# Clock_Distribution_PLL.net
KiCad netlist of a schematic drawn in Altium Designer
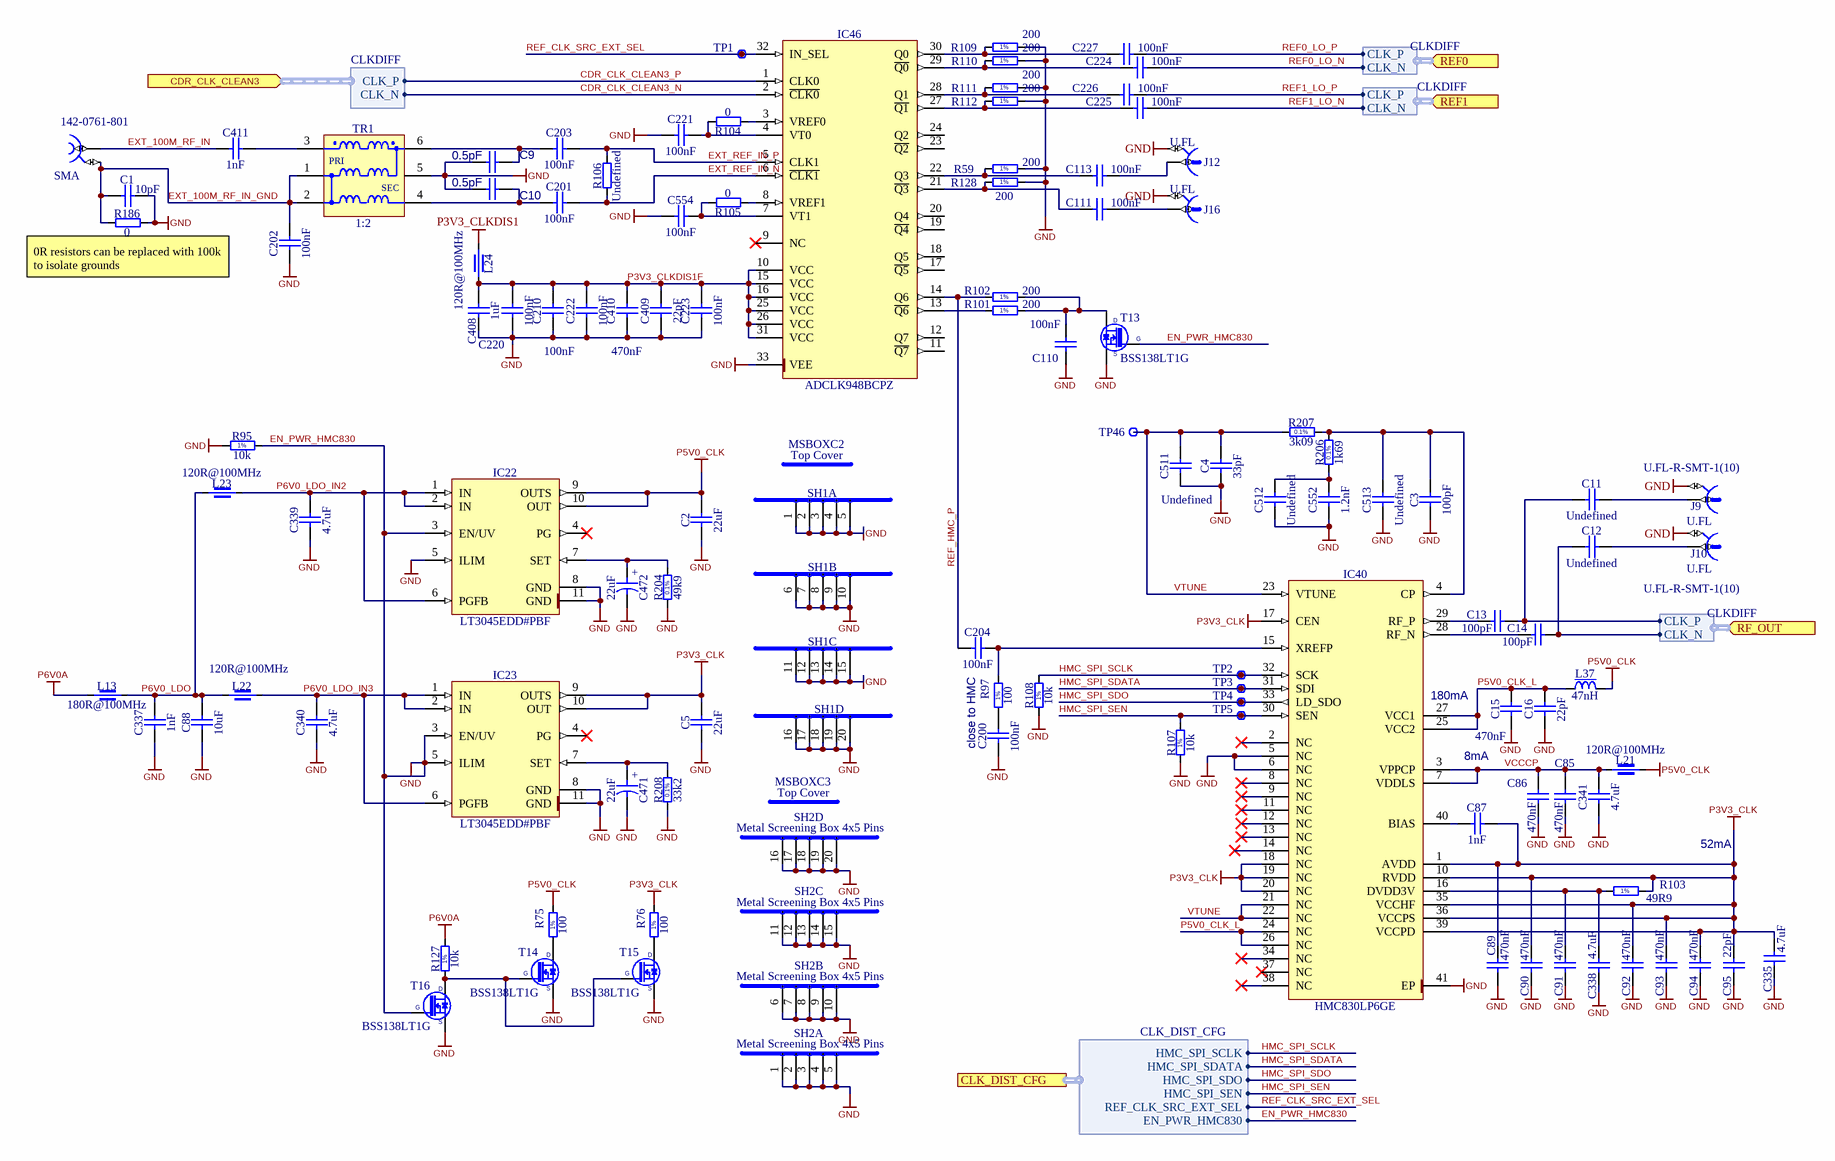
[diagram p0: Clock_Distribution_PLL.SchDoc]

(export (version "E")
  (design (tool "Eeschema 10.0.6"))
  (components
    (comp (ref "C1")
      (value "10pF")
      (footprint "CAPC1608X87N")
      (description "Non-polarised capacitor")
      (fields
        (field (name "MANUFACTURER PART NUMBER") "CC0603_10PF_50V_5%_NP0")
        (field (name "MANUFACTURER") "GENERIC")
        (field (name "AUTHOR") "CERN DEM JLC")
      )
      (libsource (lib "Capacitors") (part "Capacitor - non polarized"))
    )
    (comp (ref "C2")
      (value "22uF")
      (footprint "CAPC2012X135N")
      (description "Non-polarised capacitor")
      (fields
        (field (name "MANUFACTURER PART NUMBER") "CC0805_22UF_16V_10%_X5R")
        (field (name "MANUFACTURER") "GENERIC")
        (field (name "AUTHOR") "CERN DEM JLC")
      )
      (libsource (lib "Capacitors") (part "Capacitor - non polarized"))
    )
    (comp (ref "C3")
      (value "100pF")
      (footprint "CAPC1608X87N")
      (description "Non-polarised capacitor")
      (fields
        (field (name "MANUFACTURER PART NUMBER") "CC0603_100PF_50V_5%_NP0")
        (field (name "MANUFACTURER") "GENERIC")
        (field (name "AUTHOR") "CERN DEM JLC")
      )
      (libsource (lib "Capacitors") (part "Capacitor - non polarized"))
    )
    (comp (ref "C4")
      (value "33pF")
      (footprint "CAPC1608X87N")
      (description "Non-polarised capacitor")
      (fields
        (field (name "MANUFACTURER PART NUMBER") "CC0603_33PF_50V_5%_NP0")
        (field (name "MANUFACTURER") "GENERIC")
        (field (name "AUTHOR") "CERN DEM JLC")
      )
      (libsource (lib "Capacitors") (part "Capacitor - non polarized"))
    )
    (comp (ref "C5")
      (value "22uF")
      (footprint "CAPC2012X135N")
      (description "Non-polarised capacitor")
      (fields
        (field (name "MANUFACTURER PART NUMBER") "CC0805_22UF_16V_10%_X5R")
        (field (name "MANUFACTURER") "GENERIC")
        (field (name "AUTHOR") "CERN DEM JLC")
      )
      (libsource (lib "Capacitors") (part "Capacitor - non polarized"))
    )
    (comp (ref "C9")
      (value "0.5pF")
      (footprint "CAPC1005X55N")
      (fields
        (field (name "$$NOTCOMMONPROPERTY_GENERAL PART NUMBER") "CC0402_0.5PF_25V_0.25PF_C0G")
        (field (name "MANUFACTURER PART NUMBER") "CC0402_0.5PF_25V_0.05PF_C0G")
        (field (name "MANUFACTURER") "GENERIC")
      )
      (libsource (lib "altium-import") (part "root_0__*"))
    )
    (comp (ref "C10")
      (value "0.5pF")
      (footprint "CAPC1005X55N")
      (fields
        (field (name "$$NOTCOMMONPROPERTY_GENERAL PART NUMBER") "CC0402_0.5PF_25V_0.25PF_C0G")
        (field (name "MANUFACTURER PART NUMBER") "CC0402_0.5PF_25V_0.05PF_C0G")
        (field (name "MANUFACTURER") "GENERIC")
      )
      (libsource (lib "altium-import") (part "root_0__*"))
    )
    (comp (ref "C11")
      (value "Undefined")
      (footprint "CAPC1005X55N")
      (description "Non-polarised capacitor")
      (fields (field (name "PART NUMBER") "CC0402_NO-VALUE") (field (name "AUTHOR") "CERN DEM JLC"))
      (libsource (lib "Capacitors") (part "Capacitor - non polarized"))
    )
    (comp (ref "C12")
      (value "Undefined")
      (footprint "CAPC1005X55N")
      (description "Non-polarised capacitor")
      (fields (field (name "PART NUMBER") "CC0402_NO-VALUE") (field (name "AUTHOR") "CERN DEM JLC"))
      (libsource (lib "Capacitors") (part "Capacitor - non polarized"))
    )
    (comp (ref "C13")
      (value "100pF")
      (footprint "CAPC1608X87N")
      (description "Non-polarised capacitor")
      (fields
        (field (name "MANUFACTURER PART NUMBER") "CC0603_100PF_50V_5%_NP0")
        (field (name "MANUFACTURER") "GENERIC")
        (field (name "AUTHOR") "CERN DEM JLC")
      )
      (libsource (lib "Capacitors") (part "Capacitor - non polarized"))
    )
    (comp (ref "C14")
      (value "100pF")
      (footprint "CAPC1608X87N")
      (description "Non-polarised capacitor")
      (fields
        (field (name "MANUFACTURER PART NUMBER") "CC0603_100PF_50V_5%_NP0")
        (field (name "MANUFACTURER") "GENERIC")
        (field (name "AUTHOR") "CERN DEM JLC")
      )
      (libsource (lib "Capacitors") (part "Capacitor - non polarized"))
    )
    (comp (ref "C15")
      (value "470nF")
      (footprint "CAPC1005X55N")
      (description "Non-polarised capacitor")
      (fields
        (field (name "MANUFACTURER PART NUMBER") "CC0402_470NF_16V_10%_X5R")
        (field (name "MANUFACTURER") "GENERIC")
        (field (name "AUTHOR") "CERN DEM JLC")
      )
      (libsource (lib "Capacitors") (part "Capacitor - non polarized"))
    )
    (comp (ref "C16")
      (value "22pF")
      (footprint "CAPC1005X55N")
      (description "Non-polarised capacitor")
      (fields
        (field (name "MANUFACTURER PART NUMBER") "CC0402_22PF_50V_5%_C0G")
        (field (name "MANUFACTURER") "GENERIC")
        (field (name "AUTHOR") "CERN DEM JLC")
      )
      (libsource (lib "Capacitors") (part "Capacitor - non polarized"))
    )
    (comp (ref "C85")
      (value "470nF")
      (footprint "CAPC1005X55N")
      (description "Non-polarised capacitor")
      (fields
        (field (name "MANUFACTURER PART NUMBER") "CC0402_470NF_16V_10%_X5R")
        (field (name "MANUFACTURER") "GENERIC")
        (field (name "AUTHOR") "CERN DEM JLC")
      )
      (libsource (lib "Capacitors") (part "Capacitor - non polarized"))
    )
    (comp (ref "C86")
      (value "470nF")
      (footprint "CAPC1005X55N")
      (description "Non-polarised capacitor")
      (fields
        (field (name "MANUFACTURER PART NUMBER") "CC0402_470NF_16V_10%_X5R")
        (field (name "MANUFACTURER") "GENERIC")
        (field (name "AUTHOR") "CERN DEM JLC")
      )
      (libsource (lib "Capacitors") (part "Capacitor - non polarized"))
    )
    (comp (ref "C87")
      (value "1nF")
      (footprint "CAPC1005X55N")
      (description "Non-polarised capacitor")
      (fields
        (field (name "MANUFACTURER PART NUMBER") "CC0402_1NF_50V_10%_X7R")
        (field (name "MANUFACTURER") "GENERIC")
        (field (name "AUTHOR") "CERN DEM JLC")
      )
      (libsource (lib "Capacitors") (part "Capacitor - non polarized"))
    )
    (comp (ref "C88")
      (value "10uF")
      (footprint "CAPC3216X180N")
      (description "Non-polarised capacitor")
      (fields
        (field (name "MANUFACTURER PART NUMBER") "CC1206_10uF_25V_10%_X7R")
        (field (name "MANUFACTURER") "GENERIC")
        (field (name "AUTHOR") "CERN DEM JLC")
      )
      (libsource (lib "Capacitors") (part "Capacitor - non polarized"))
    )
    (comp (ref "C89")
      (value "470nF")
      (footprint "CAPC1005X55N")
      (description "Non-polarised capacitor")
      (fields
        (field (name "MANUFACTURER PART NUMBER") "CC0402_470NF_16V_10%_X5R")
        (field (name "MANUFACTURER") "GENERIC")
        (field (name "AUTHOR") "CERN DEM JLC")
      )
      (libsource (lib "Capacitors") (part "Capacitor - non polarized"))
    )
    (comp (ref "C90")
      (value "470nF")
      (footprint "CAPC1005X55N")
      (description "Non-polarised capacitor")
      (fields
        (field (name "MANUFACTURER PART NUMBER") "CC0402_470NF_16V_10%_X5R")
        (field (name "MANUFACTURER") "GENERIC")
        (field (name "AUTHOR") "CERN DEM JLC")
      )
      (libsource (lib "Capacitors") (part "Capacitor - non polarized"))
    )
    (comp (ref "C91")
      (value "470nF")
      (footprint "CAPC1005X55N")
      (description "Non-polarised capacitor")
      (fields
        (field (name "MANUFACTURER PART NUMBER") "CC0402_470NF_16V_10%_X5R")
        (field (name "MANUFACTURER") "GENERIC")
        (field (name "AUTHOR") "CERN DEM JLC")
      )
      (libsource (lib "Capacitors") (part "Capacitor - non polarized"))
    )
    (comp (ref "C92")
      (value "470nF")
      (footprint "CAPC1005X55N")
      (description "Non-polarised capacitor")
      (fields
        (field (name "MANUFACTURER PART NUMBER") "CC0402_470NF_16V_10%_X5R")
        (field (name "MANUFACTURER") "GENERIC")
        (field (name "AUTHOR") "CERN DEM JLC")
      )
      (libsource (lib "Capacitors") (part "Capacitor - non polarized"))
    )
    (comp (ref "C93")
      (value "470nF")
      (footprint "CAPC1005X55N")
      (description "Non-polarised capacitor")
      (fields
        (field (name "MANUFACTURER PART NUMBER") "CC0402_470NF_16V_10%_X5R")
        (field (name "MANUFACTURER") "GENERIC")
        (field (name "AUTHOR") "CERN DEM JLC")
      )
      (libsource (lib "Capacitors") (part "Capacitor - non polarized"))
    )
    (comp (ref "C94")
      (value "470nF")
      (footprint "CAPC1005X55N")
      (description "Non-polarised capacitor")
      (fields
        (field (name "MANUFACTURER PART NUMBER") "CC0402_470NF_16V_10%_X5R")
        (field (name "MANUFACTURER") "GENERIC")
        (field (name "AUTHOR") "CERN DEM JLC")
      )
      (libsource (lib "Capacitors") (part "Capacitor - non polarized"))
    )
    (comp (ref "C95")
      (value "22pF")
      (footprint "CAPC1005X55N")
      (description "Non-polarised capacitor")
      (fields
        (field (name "MANUFACTURER PART NUMBER") "CC0402_22PF_50V_5%_C0G")
        (field (name "MANUFACTURER") "GENERIC")
        (field (name "AUTHOR") "CERN DEM JLC")
      )
      (libsource (lib "Capacitors") (part "Capacitor - non polarized"))
    )
    (comp (ref "C110")
      (value "100nF")
      (footprint "CAPC0603X33N")
      (description "Non-polarised capacitor")
      (fields
        (field (name "MANUFACTURER PART NUMBER") "CC0201_100NF_6.3V_10%_X5R")
        (field (name "MANUFACTURER") "GENERIC")
        (field (name "AUTHOR") "CERN DEM JLC")
      )
      (libsource (lib "Capacitors") (part "Capacitor - non polarized"))
    )
    (comp (ref "C111")
      (value "100nF")
      (footprint "CAPC0603X33N")
      (description "Non-polarised capacitor")
      (fields
        (field (name "MANUFACTURER PART NUMBER") "CC0201_100NF_6.3V_10%_X5R")
        (field (name "MANUFACTURER") "GENERIC")
        (field (name "AUTHOR") "CERN DEM JLC")
      )
      (libsource (lib "Capacitors") (part "Capacitor - non polarized"))
    )
    (comp (ref "C113")
      (value "100nF")
      (footprint "CAPC0603X33N")
      (description "Non-polarised capacitor")
      (fields
        (field (name "MANUFACTURER PART NUMBER") "CC0201_100NF_6.3V_10%_X5R")
        (field (name "MANUFACTURER") "GENERIC")
        (field (name "AUTHOR") "CERN DEM JLC")
      )
      (libsource (lib "Capacitors") (part "Capacitor - non polarized"))
    )
    (comp (ref "C200")
      (value "100nF")
      (footprint "CAPC0603X33N")
      (description "Non-polarised capacitor")
      (fields
        (field (name "MANUFACTURER PART NUMBER") "CC0201_100NF_6.3V_10%_X5R")
        (field (name "MANUFACTURER") "GENERIC")
        (field (name "AUTHOR") "CERN DEM JLC")
      )
      (libsource (lib "Capacitors") (part "Capacitor - non polarized"))
    )
    (comp (ref "C201")
      (value "100nF")
      (footprint "CAPC0603X33N")
      (description "Non-polarised capacitor")
      (fields
        (field (name "MANUFACTURER PART NUMBER") "CC0201_100NF_6.3V_10%_X5R")
        (field (name "MANUFACTURER") "GENERIC")
        (field (name "AUTHOR") "CERN DEM JLC")
      )
      (libsource (lib "Capacitors") (part "Capacitor - non polarized"))
    )
    (comp (ref "C202")
      (value "100nF")
      (footprint "CAPC0603X33N")
      (description "Non-polarised capacitor")
      (fields
        (field (name "MANUFACTURER PART NUMBER") "CC0201_100NF_6.3V_10%_X5R")
        (field (name "MANUFACTURER") "GENERIC")
        (field (name "AUTHOR") "CERN DEM JLC")
      )
      (libsource (lib "Capacitors") (part "Capacitor - non polarized"))
    )
    (comp (ref "C203")
      (value "100nF")
      (footprint "CAPC0603X33N")
      (description "Non-polarised capacitor")
      (fields
        (field (name "MANUFACTURER PART NUMBER") "CC0201_100NF_6.3V_10%_X5R")
        (field (name "MANUFACTURER") "GENERIC")
        (field (name "AUTHOR") "CERN DEM JLC")
      )
      (libsource (lib "Capacitors") (part "Capacitor - non polarized"))
    )
    (comp (ref "C204")
      (value "100nF")
      (footprint "CAPC0603X33N")
      (description "Non-polarised capacitor")
      (fields
        (field (name "MANUFACTURER PART NUMBER") "CC0201_100NF_6.3V_10%_X5R")
        (field (name "MANUFACTURER") "GENERIC")
        (field (name "AUTHOR") "CERN DEM JLC")
      )
      (libsource (lib "Capacitors") (part "Capacitor - non polarized"))
    )
    (comp (ref "C210")
      (value "100nF")
      (footprint "CAPC0603X33N")
      (description "Non-polarised capacitor")
      (fields
        (field (name "MANUFACTURER PART NUMBER") "CC0201_100NF_6.3V_10%_X5R")
        (field (name "MANUFACTURER") "GENERIC")
        (field (name "AUTHOR") "CERN DEM JLC")
      )
      (libsource (lib "Capacitors") (part "Capacitor - non polarized"))
    )
    (comp (ref "C220")
      (value "100nF")
      (footprint "CAPC0603X33N")
      (description "Non-polarised capacitor")
      (fields
        (field (name "MANUFACTURER PART NUMBER") "CC0201_100NF_6.3V_10%_X5R")
        (field (name "MANUFACTURER") "GENERIC")
        (field (name "AUTHOR") "CERN DEM JLC")
      )
      (libsource (lib "Capacitors") (part "Capacitor - non polarized"))
    )
    (comp (ref "C221")
      (value "100nF")
      (footprint "CAPC0603X33N")
      (description "Non-polarised capacitor")
      (fields
        (field (name "MANUFACTURER PART NUMBER") "CC0201_100NF_6.3V_10%_X5R")
        (field (name "MANUFACTURER") "GENERIC")
        (field (name "AUTHOR") "CERN DEM JLC")
      )
      (libsource (lib "Capacitors") (part "Capacitor - non polarized"))
    )
    (comp (ref "C222")
      (value "100nF")
      (footprint "CAPC0603X33N")
      (description "Non-polarised capacitor")
      (fields
        (field (name "MANUFACTURER PART NUMBER") "CC0201_100NF_6.3V_10%_X5R")
        (field (name "MANUFACTURER") "GENERIC")
        (field (name "AUTHOR") "CERN DEM JLC")
      )
      (libsource (lib "Capacitors") (part "Capacitor - non polarized"))
    )
    (comp (ref "C223")
      (value "100nF")
      (footprint "CAPC0603X33N")
      (description "Non-polarised capacitor")
      (fields
        (field (name "MANUFACTURER PART NUMBER") "CC0201_100NF_6.3V_10%_X5R")
        (field (name "MANUFACTURER") "GENERIC")
        (field (name "AUTHOR") "CERN DEM JLC")
      )
      (libsource (lib "Capacitors") (part "Capacitor - non polarized"))
    )
    (comp (ref "C224")
      (value "100nF")
      (footprint "CAPC0603X33N")
      (description "Non-polarised capacitor")
      (fields
        (field (name "MANUFACTURER PART NUMBER") "CC0201_100NF_6.3V_10%_X5R")
        (field (name "MANUFACTURER") "GENERIC")
        (field (name "AUTHOR") "CERN DEM JLC")
      )
      (libsource (lib "Capacitors") (part "Capacitor - non polarized"))
    )
    (comp (ref "C225")
      (value "100nF")
      (footprint "CAPC0603X33N")
      (description "Non-polarised capacitor")
      (fields
        (field (name "MANUFACTURER PART NUMBER") "CC0201_100NF_6.3V_10%_X5R")
        (field (name "MANUFACTURER") "GENERIC")
        (field (name "AUTHOR") "CERN DEM JLC")
      )
      (libsource (lib "Capacitors") (part "Capacitor - non polarized"))
    )
    (comp (ref "C226")
      (value "100nF")
      (footprint "CAPC0603X33N")
      (description "Non-polarised capacitor")
      (fields
        (field (name "MANUFACTURER PART NUMBER") "CC0201_100NF_6.3V_10%_X5R")
        (field (name "MANUFACTURER") "GENERIC")
        (field (name "AUTHOR") "CERN DEM JLC")
      )
      (libsource (lib "Capacitors") (part "Capacitor - non polarized"))
    )
    (comp (ref "C227")
      (value "100nF")
      (footprint "CAPC0603X33N")
      (description "Non-polarised capacitor")
      (fields
        (field (name "MANUFACTURER PART NUMBER") "CC0201_100NF_6.3V_10%_X5R")
        (field (name "MANUFACTURER") "GENERIC")
        (field (name "AUTHOR") "CERN DEM JLC")
      )
      (libsource (lib "Capacitors") (part "Capacitor - non polarized"))
    )
    (comp (ref "C335")
      (value "4.7uF")
      (footprint "CAPC1608X90N")
      (description "Non-polarised capacitor")
      (fields
        (field (name "MANUFACTURER PART NUMBER") "CC0603_4.7UF_25V_10%_X5R")
        (field (name "MANUFACTURER") "GENERIC")
        (field (name "AUTHOR") "CERN DEM JLC")
      )
      (libsource (lib "Capacitors") (part "Capacitor - non polarized"))
    )
    (comp (ref "C337")
      (value "1nF")
      (footprint "CAPC1608X90N")
      (description "Non-polarised capacitor")
      (fields
        (field (name "MANUFACTURER PART NUMBER") "CC0603_1NF_50V_5%_NP0")
        (field (name "MANUFACTURER") "GENERIC")
        (field (name "AUTHOR") "CERN DEM JLC")
      )
      (libsource (lib "Capacitors") (part "Capacitor - non polarized"))
    )
    (comp (ref "C338")
      (value "4.7uF")
      (footprint "CAPC1608X90N")
      (description "Non-polarised capacitor")
      (fields
        (field (name "MANUFACTURER PART NUMBER") "CC0603_4.7UF_25V_10%_X5R")
        (field (name "MANUFACTURER") "GENERIC")
        (field (name "AUTHOR") "CERN DEM JLC")
      )
      (libsource (lib "Capacitors") (part "Capacitor - non polarized"))
    )
    (comp (ref "C339")
      (value "4.7uF")
      (footprint "CAPC1608X90N")
      (description "Non-polarised capacitor")
      (fields
        (field (name "MANUFACTURER PART NUMBER") "CC0603_4.7UF_25V_10%_X5R")
        (field (name "MANUFACTURER") "GENERIC")
        (field (name "AUTHOR") "CERN DEM JLC")
      )
      (libsource (lib "Capacitors") (part "Capacitor - non polarized"))
    )
    (comp (ref "C340")
      (value "4.7uF")
      (footprint "CAPC1608X90N")
      (description "Non-polarised capacitor")
      (fields
        (field (name "MANUFACTURER PART NUMBER") "CC0603_4.7UF_25V_10%_X5R")
        (field (name "MANUFACTURER") "GENERIC")
        (field (name "AUTHOR") "CERN DEM JLC")
      )
      (libsource (lib "Capacitors") (part "Capacitor - non polarized"))
    )
    (comp (ref "C341")
      (value "4.7uF")
      (footprint "CAPC1608X90N")
      (description "Non-polarised capacitor")
      (fields
        (field (name "MANUFACTURER PART NUMBER") "CC0603_4.7UF_25V_10%_X5R")
        (field (name "MANUFACTURER") "GENERIC")
        (field (name "AUTHOR") "CERN DEM JLC")
      )
      (libsource (lib "Capacitors") (part "Capacitor - non polarized"))
    )
    (comp (ref "C408")
      (value "1uF")
      (footprint "CAPC1005X55N")
      (description "Non-polarised capacitor")
      (fields
        (field (name "MANUFACTURER PART NUMBER") "CC0402_1UF_16V_10%_X5R")
        (field (name "MANUFACTURER") "GENERIC")
        (field (name "AUTHOR") "CERN DEM JLC")
      )
      (libsource (lib "Capacitors") (part "Capacitor - non polarized"))
    )
    (comp (ref "C409")
      (value "22pF")
      (footprint "CAPC1005X55N")
      (description "Non-polarised capacitor")
      (fields
        (field (name "MANUFACTURER PART NUMBER") "CC0402_22PF_50V_5%_C0G")
        (field (name "MANUFACTURER") "GENERIC")
        (field (name "AUTHOR") "CERN DEM JLC")
      )
      (libsource (lib "Capacitors") (part "Capacitor - non polarized"))
    )
    (comp (ref "C410")
      (value "470nF")
      (footprint "CAPC1005X55N")
      (description "Non-polarised capacitor")
      (fields
        (field (name "MANUFACTURER PART NUMBER") "CC0402_470NF_16V_10%_X5R")
        (field (name "MANUFACTURER") "GENERIC")
        (field (name "AUTHOR") "CERN DEM JLC")
      )
      (libsource (lib "Capacitors") (part "Capacitor - non polarized"))
    )
    (comp (ref "C411")
      (value "1nF")
      (footprint "CAPC1005X55N")
      (description "Non-polarised capacitor")
      (fields
        (field (name "MANUFACTURER PART NUMBER") "CC0402_1NF_50V_10%_X7R")
        (field (name "MANUFACTURER") "GENERIC")
        (field (name "AUTHOR") "CERN DEM JLC")
      )
      (libsource (lib "Capacitors") (part "Capacitor - non polarized"))
    )
    (comp (ref "C471")
      (value "22uF")
      (footprint "CAPMP3216X180N")
      (description "Polarised capacitor")
      (fields
        (field (name "MANUFACTURER PART NUMBER") "CTE3216-18_22UF_6.3V_10%_LESR0900")
        (field (name "MANUFACTURER") "GENERIC")
        (field (name "AUTHOR") "CERN DEM JLC")
      )
      (libsource (lib "Capacitors") (part "Capacitor - polarized"))
    )
    (comp (ref "C472")
      (value "22uF")
      (footprint "CAPMP3216X180N")
      (description "Polarised capacitor")
      (fields
        (field (name "MANUFACTURER PART NUMBER") "CTE3216-18_22UF_6.3V_10%_LESR0900")
        (field (name "MANUFACTURER") "GENERIC")
        (field (name "AUTHOR") "CERN DEM JLC")
      )
      (libsource (lib "Capacitors") (part "Capacitor - polarized"))
    )
    (comp (ref "C511")
      (value "Undefined")
      (footprint "CAPC2012X135N")
      (description "Non-polarised capacitor")
      (fields
        (field (name "MANUFACTURER PART NUMBER") "CC0805_NO-VALUE")
        (field (name "AUTHOR") "CERN DEM JLC")
      )
      (libsource (lib "Capacitors") (part "Capacitor - non polarized"))
    )
    (comp (ref "C512")
      (value "Undefined")
      (footprint "CAPC2012X135N")
      (description "Non-polarised capacitor")
      (fields
        (field (name "MANUFACTURER PART NUMBER") "CC0805_NO-VALUE")
        (field (name "AUTHOR") "CERN DEM JLC")
      )
      (libsource (lib "Capacitors") (part "Capacitor - non polarized"))
    )
    (comp (ref "C513")
      (value "Undefined")
      (footprint "CAPC2012X135N")
      (description "Non-polarised capacitor")
      (fields
        (field (name "MANUFACTURER PART NUMBER") "CC0805_NO-VALUE")
        (field (name "AUTHOR") "CERN DEM JLC")
      )
      (libsource (lib "Capacitors") (part "Capacitor - non polarized"))
    )
    (comp (ref "C552")
      (value "1.2nF")
      (footprint "CAPC3216X140N")
      (description "Non-polarised capacitor")
      (fields
        (field (name "MANUFACTURER PART NUMBER") "CC1206_1.2NF_50V_5%_NP0")
        (field (name "MANUFACTURER") "GENERIC")
        (field (name "AUTHOR") "CERN DEM JLC")
      )
      (libsource (lib "Capacitors") (part "Capacitor - non polarized"))
    )
    (comp (ref "C554")
      (value "100nF")
      (footprint "CAPC0603X33N")
      (description "Non-polarised capacitor")
      (fields
        (field (name "MANUFACTURER PART NUMBER") "CC0201_100NF_6.3V_10%_X5R")
        (field (name "MANUFACTURER") "GENERIC")
        (field (name "AUTHOR") "CERN DEM JLC")
      )
      (libsource (lib "Capacitors") (part "Capacitor - non polarized"))
    )
    (comp (ref "IC22")
      (value "LT3045EDD#PBF")
      (footprint "SON50P300X300X80-11N-R175X248")
      (description "20V, 500mA, Ultralow Noise, Ultrahigh PSRR Linear Regulator")
      (fields (field (name "MANUFACTURER") "LINEAR TECHNOLOGY") (field (name "AUTHOR") "CERN DEM JLC"))
      (libsource (lib "ICs And Semiconductors") (part "LT3045EDD"))
    )
    (comp (ref "IC23")
      (value "LT3045EDD#PBF")
      (footprint "SON50P300X300X80-11N-R175X248")
      (description "20V, 500mA, Ultralow Noise, Ultrahigh PSRR Linear Regulator")
      (fields (field (name "MANUFACTURER") "LINEAR TECHNOLOGY") (field (name "AUTHOR") "CERN DEM JLC"))
      (libsource (lib "ICs And Semiconductors") (part "LT3045EDD"))
    )
    (comp (ref "IC40")
      (value "HMC830LP6GE")
      (footprint "QFN50P600X600X90-41N-S475")
      (description "Fractional-N PLL With Integrated VCO, 25 to 3000MHz")
      (fields (field (name "MANUFACTURER") "HITTITE MICROWAVE CORP") (field (name "AUTHOR") "CERN DEM JMW"))
      (libsource (lib "ICs And Semiconductors") (part "HMC830LP6GE"))
    )
    (comp (ref "IC46")
      (value "ADCLK948BCPZ")
      (footprint "QFN50P500X500X80-33N-S285")
      (description "Two Selectable Inputs, 8 LVPECL Outputs, SiGe Clock Fanout Buffer")
      (fields (field (name "MANUFACTURER") "ANALOG DEVICES") (field (name "AUTHOR") "CERN DEM MR"))
      (libsource (lib "ICs And Semiconductors") (part "ADCLK948"))
    )
    (comp (ref "J4")
      (value "SMA")
      (footprint "CINCH_142-0761-801")
      (fields
        (field (name "FAMILY") "SMA")
        (field (name "MANUFACTURER PART NUMBER") "142-0761-801")
        (field (name "MANUFACTURER") "CINCH CONNECTIVITY")
        (field (name "PART NUMBER") "CINCH_142-0761-801")
        (field (name "AUTHOR") "CERN DEM JLC")
      )
      (libsource (lib "Connectors") (part "Coax_1Female_1Shield"))
    )
    (comp (ref "J9")
      (value "U.FL")
      (footprint "HIROSE_U.FL-R-SMT-1(10)")
      (fields
        (field (name "FAMILY") "U.FL")
        (field (name "MANUFACTURER PART NUMBER") "U.FL-R-SMT-1(10)")
        (field (name "MANUFACTURER") "HIROSE (HRS)")
        (field (name "PART NUMBER") "HIROSE_U.FL-R-SMT-1(10)")
        (field (name "AUTHOR") "CERN DEM JLC")
      )
      (libsource (lib "Connectors") (part "Coax_1Male_1Shield"))
    )
    (comp (ref "J10")
      (value "U.FL")
      (footprint "HIROSE_U.FL-R-SMT-1(10)")
      (fields
        (field (name "FAMILY") "U.FL")
        (field (name "MANUFACTURER PART NUMBER") "U.FL-R-SMT-1(10)")
        (field (name "MANUFACTURER") "HIROSE (HRS)")
        (field (name "PART NUMBER") "HIROSE_U.FL-R-SMT-1(10)")
        (field (name "AUTHOR") "CERN DEM JLC")
      )
      (libsource (lib "Connectors") (part "Coax_1Male_1Shield"))
    )
    (comp (ref "J12")
      (value "U.FL")
      (footprint "HIROSE_U.FL-R-SMT-1(10)")
      (fields
        (field (name "MANUFACTURER PART NUMBER") "U.FL-R-SMT-1(10)")
        (field (name "MANUFACTURER") "HIROSE (HRS)")
        (field (name "PART NUMBER") "HIROSE_U.FL-R-SMT-1(10)")
        (field (name "AUTHOR") "CERN DEM JLC")
      )
      (libsource (lib "Connectors") (part "Coax_1Male_1Shield"))
    )
    (comp (ref "J16")
      (value "U.FL")
      (footprint "HIROSE_U.FL-R-SMT-1(10)")
      (fields
        (field (name "MANUFACTURER PART NUMBER") "U.FL-R-SMT-1(10)")
        (field (name "MANUFACTURER") "HIROSE (HRS)")
        (field (name "PART NUMBER") "HIROSE_U.FL-R-SMT-1(10)")
        (field (name "AUTHOR") "CERN DEM JLC")
      )
      (libsource (lib "Connectors") (part "Coax_1Male_1Shield"))
    )
    (comp (ref "L13")
      (value "180R@100MHz")
      (footprint "INDC4516X180N")
      (fields
        (field (name "MANUFACTURER PART NUMBER") "BLM41PG181SN1L")
        (field (name "MANUFACTURER") "MURATA")
        (field (name "PART NUMBER") "IND1806_MURATA_BLM41PG181SN1L")
        (field (name "AUTHOR") "CERN DEM JLC")
      )
      (libsource (lib "Inductors & Transformers") (part "Ferrite Bead"))
    )
    (comp (ref "L21")
      (value "120R@100MHz")
      (footprint "INDC1608X95N")
      (fields
        (field (name "MANUFACTURER PART NUMBER") "BLM18PG121SN1D")
        (field (name "MANUFACTURER") "MURATA")
        (field (name "PART NUMBER") "IND0603_MURATA_BLM18PG121SN1D")
        (field (name "AUTHOR") "CERN DEM BC")
      )
      (libsource (lib "Inductors & Transformers") (part "Ferrite Bead"))
    )
    (comp (ref "L22")
      (value "120R@100MHz")
      (footprint "INDC1608X95N")
      (fields
        (field (name "MANUFACTURER PART NUMBER") "BLM18PG121SN1D")
        (field (name "MANUFACTURER") "MURATA")
        (field (name "PART NUMBER") "IND0603_MURATA_BLM18PG121SN1D")
        (field (name "AUTHOR") "CERN DEM BC")
      )
      (libsource (lib "Inductors & Transformers") (part "Ferrite Bead"))
    )
    (comp (ref "L23")
      (value "120R@100MHz")
      (footprint "INDC1608X95N")
      (fields
        (field (name "MANUFACTURER PART NUMBER") "BLM18PG121SN1D")
        (field (name "MANUFACTURER") "MURATA")
        (field (name "PART NUMBER") "IND0603_MURATA_BLM18PG121SN1D")
        (field (name "AUTHOR") "CERN DEM BC")
      )
      (libsource (lib "Inductors & Transformers") (part "Ferrite Bead"))
    )
    (comp (ref "L24")
      (value "120R@100MHz")
      (footprint "INDC1608X95N")
      (fields
        (field (name "MANUFACTURER PART NUMBER") "BLM18PG121SN1D")
        (field (name "MANUFACTURER") "MURATA")
        (field (name "PART NUMBER") "IND0603_MURATA_BLM18PG121SN1D")
        (field (name "AUTHOR") "CERN DEM BC")
      )
      (libsource (lib "") (part "Ferrite Bead_1"))
    )
    (comp (ref "L37")
      (value "47nH")
      (footprint "INDC2014X145N")
      (description "Inductor With Core")
      (fields
        (field (name "MANUFACTURER PART NUMBER") "B82498B3470J")
        (field (name "MANUFACTURER") "EPCOS")
        (field (name "AUTHOR") "CERN DEM JLC")
      )
      (libsource (lib "Inductors & Transformers") (part "Inductor With Magnetic core"))
    )
    (comp (ref "MSBOXC2")
      (value "Top Cover")
      (footprint "MSBOX_WURTH_36003300")
      (description "Metal Screening Box - Top Cover 0 Pin")
      (fields
        (field (name "PART NUMBER") "MSBOX_WURTH_36003300")
        (field (name "MANUFACTURER") "WURTH")
        (field (name "AUTHOR") "CERN DEM JLC")
      )
      (libsource (lib "Eletro-mechanical") (part "Metal Screening Box - Top Cover"))
    )
    (comp (ref "MSBOXC3")
      (value "Top Cover")
      (footprint "MSBOX_WURTH_36003300")
      (description "Metal Screening Box - Top Cover 0 Pin")
      (fields
        (field (name "PART NUMBER") "MSBOX_WURTH_36003300")
        (field (name "MANUFACTURER") "WURTH")
        (field (name "AUTHOR") "CERN DEM JLC")
      )
      (libsource (lib "Eletro-mechanical") (part "Metal Screening Box - Top Cover"))
    )
    (comp (ref "R59")
      (value "200")
      (footprint "RESC1005X40N")
      (description "Resistor - 1%")
      (fields
        (field (name "MANUFACTURER PART NUMBER") "R0402_200R_1%_0.0625W_100PPM")
        (field (name "MANUFACTURER") "GENERIC")
        (field (name "AUTHOR") "CERN DEM JLC")
      )
      (libsource (lib "Resistors") (part "Resistor - 1%"))
    )
    (comp (ref "R75")
      (value "100")
      (footprint "RESC1005X40N")
      (description "Resistor - 1%")
      (fields
        (field (name "MANUFACTURER PART NUMBER") "R0402_100R_1%_0.0625W_100PPM")
        (field (name "MANUFACTURER") "GENERIC")
        (field (name "AUTHOR") "CERN DEM JLC")
      )
      (libsource (lib "Resistors") (part "Resistor - 1%"))
    )
    (comp (ref "R76")
      (value "100")
      (footprint "RESC1005X40N")
      (description "Resistor - 1%")
      (fields
        (field (name "MANUFACTURER PART NUMBER") "R0402_100R_1%_0.0625W_100PPM")
        (field (name "MANUFACTURER") "GENERIC")
        (field (name "AUTHOR") "CERN DEM JLC")
      )
      (libsource (lib "Resistors") (part "Resistor - 1%"))
    )
    (comp (ref "R95")
      (value "10k")
      (footprint "RESC1005X40N")
      (description "Resistor - 1%")
      (fields
        (field (name "MANUFACTURER PART NUMBER") "R0402_10K_1%_0.0625W_100PPM")
        (field (name "MANUFACTURER") "GENERIC")
        (field (name "AUTHOR") "CERN DEM JLC")
      )
      (libsource (lib "Resistors") (part "Resistor - 1%"))
    )
    (comp (ref "R97")
      (value "100")
      (footprint "RESC1005X40N")
      (description "Resistor - 1%")
      (fields
        (field (name "MANUFACTURER PART NUMBER") "R0402_100R_1%_0.0625W_100PPM")
        (field (name "MANUFACTURER") "GENERIC")
        (field (name "AUTHOR") "CERN DEM JLC")
      )
      (libsource (lib "Resistors") (part "Resistor - 1%"))
    )
    (comp (ref "R101")
      (value "200")
      (footprint "RESC1005X40N")
      (description "Resistor - 1%")
      (fields
        (field (name "MANUFACTURER PART NUMBER") "R0402_200R_1%_0.0625W_100PPM")
        (field (name "MANUFACTURER") "GENERIC")
        (field (name "AUTHOR") "CERN DEM JLC")
      )
      (libsource (lib "Resistors") (part "Resistor - 1%"))
    )
    (comp (ref "R102")
      (value "200")
      (footprint "RESC1005X40N")
      (description "Resistor - 1%")
      (fields
        (field (name "MANUFACTURER PART NUMBER") "R0402_200R_1%_0.0625W_100PPM")
        (field (name "MANUFACTURER") "GENERIC")
        (field (name "AUTHOR") "CERN DEM JLC")
      )
      (libsource (lib "Resistors") (part "Resistor - 1%"))
    )
    (comp (ref "R103")
      (value "49R9")
      (footprint "RESC1005X40N")
      (description "Resistor - 1%")
      (fields
        (field (name "MANUFACTURER PART NUMBER") "R0402_49R9_1%_0.0625W_100PPM")
        (field (name "MANUFACTURER") "GENERIC")
        (field (name "AUTHOR") "CERN DEM JLC")
      )
      (libsource (lib "Resistors") (part "Resistor - 1%"))
    )
    (comp (ref "R104")
      (value "0")
      (footprint "RESC1005X40N")
      (description "Resistor")
      (fields
        (field (name "MANUFACTURER PART NUMBER") "R0402_0R_JUMPER")
        (field (name "MANUFACTURER") "GENERIC")
        (field (name "AUTHOR") "CERN DEM JLC")
      )
      (libsource (lib "Resistors") (part "Resistor"))
    )
    (comp (ref "R105")
      (value "0")
      (footprint "RESC1005X40N")
      (description "Resistor")
      (fields
        (field (name "MANUFACTURER PART NUMBER") "R0402_0R_JUMPER")
        (field (name "MANUFACTURER") "GENERIC")
        (field (name "AUTHOR") "CERN DEM JLC")
      )
      (libsource (lib "Resistors") (part "Resistor"))
    )
    (comp (ref "R106")
      (value "Undefined")
      (footprint "RESC1005X40N")
      (description "Resistor")
      (fields
        (field (name "MANUFACTURER PART NUMBER") "R0402_NO-VALUE")
        (field (name "AUTHOR") "CERN DEM JLC")
      )
      (libsource (lib "Resistors") (part "Resistor"))
    )
    (comp (ref "R107")
      (value "10k")
      (footprint "RESC1005X40N")
      (description "Resistor - 1%")
      (fields
        (field (name "MANUFACTURER PART NUMBER") "R0402_10K_1%_0.0625W_100PPM")
        (field (name "MANUFACTURER") "GENERIC")
        (field (name "AUTHOR") "CERN DEM JLC")
      )
      (libsource (lib "Resistors") (part "Resistor - 1%"))
    )
    (comp (ref "R108")
      (value "10k")
      (footprint "RESC1005X40N")
      (description "Resistor - 1%")
      (fields
        (field (name "MANUFACTURER PART NUMBER") "R0402_10K_1%_0.0625W_100PPM")
        (field (name "MANUFACTURER") "GENERIC")
        (field (name "AUTHOR") "CERN DEM JLC")
      )
      (libsource (lib "Resistors") (part "Resistor - 1%"))
    )
    (comp (ref "R109")
      (value "200")
      (footprint "RESC1005X40N")
      (description "Resistor - 1%")
      (fields
        (field (name "MANUFACTURER PART NUMBER") "R0402_200R_1%_0.0625W_100PPM")
        (field (name "MANUFACTURER") "GENERIC")
        (field (name "AUTHOR") "CERN DEM JLC")
      )
      (libsource (lib "Resistors") (part "Resistor - 1%"))
    )
    (comp (ref "R110")
      (value "200")
      (footprint "RESC1005X40N")
      (description "Resistor - 1%")
      (fields
        (field (name "MANUFACTURER PART NUMBER") "R0402_200R_1%_0.0625W_100PPM")
        (field (name "MANUFACTURER") "GENERIC")
        (field (name "AUTHOR") "CERN DEM JLC")
      )
      (libsource (lib "Resistors") (part "Resistor - 1%"))
    )
    (comp (ref "R111")
      (value "200")
      (footprint "RESC1005X40N")
      (description "Resistor - 1%")
      (fields
        (field (name "MANUFACTURER PART NUMBER") "R0402_200R_1%_0.0625W_100PPM")
        (field (name "MANUFACTURER") "GENERIC")
        (field (name "AUTHOR") "CERN DEM JLC")
      )
      (libsource (lib "Resistors") (part "Resistor - 1%"))
    )
    (comp (ref "R112")
      (value "200")
      (footprint "RESC1005X40N")
      (description "Resistor - 1%")
      (fields
        (field (name "MANUFACTURER PART NUMBER") "R0402_200R_1%_0.0625W_100PPM")
        (field (name "MANUFACTURER") "GENERIC")
        (field (name "AUTHOR") "CERN DEM JLC")
      )
      (libsource (lib "Resistors") (part "Resistor - 1%"))
    )
    (comp (ref "R127")
      (value "10k")
      (footprint "RESC1005X40N")
      (description "Resistor - 1%")
      (fields
        (field (name "MANUFACTURER PART NUMBER") "R0402_10K_1%_0.0625W_100PPM")
        (field (name "MANUFACTURER") "GENERIC")
        (field (name "AUTHOR") "CERN DEM JLC")
      )
      (libsource (lib "Resistors") (part "Resistor - 1%"))
    )
    (comp (ref "R128")
      (value "200")
      (footprint "RESC1005X40N")
      (description "Resistor - 1%")
      (fields
        (field (name "MANUFACTURER PART NUMBER") "R0402_200R_1%_0.0625W_100PPM")
        (field (name "MANUFACTURER") "GENERIC")
        (field (name "AUTHOR") "CERN DEM JLC")
      )
      (libsource (lib "Resistors") (part "Resistor - 1%"))
    )
    (comp (ref "R186")
      (value "0")
      (footprint "RESC1005X40N")
      (description "Resistor")
      (fields
        (field (name "MANUFACTURER PART NUMBER") "R0402_0R_JUMPER")
        (field (name "MANUFACTURER") "GENERIC")
        (field (name "AUTHOR") "CERN DEM JLC")
      )
      (libsource (lib "Resistors") (part "Resistor"))
    )
    (comp (ref "R204")
      (value "49k9")
      (footprint "RESC1608X55N")
      (description "Resistor - 0.1%")
      (fields
        (field (name "MANUFACTURER PART NUMBER") "R0603_49K9_0.1%_0.063W_10PPM")
        (field (name "MANUFACTURER") "GENERIC")
        (field (name "AUTHOR") "CERN DEM JLC")
      )
      (libsource (lib "Resistors") (part "Resistor - 0.1%"))
    )
    (comp (ref "R206")
      (value "1k69")
      (footprint "RESC1608X55N")
      (description "Resistor - 0.1%")
      (fields
        (field (name "MANUFACTURER PART NUMBER") "R0603_1K69_0.1%_0.063W_10PPM")
        (field (name "MANUFACTURER") "GENERIC")
        (field (name "AUTHOR") "CERN DEM JLC")
      )
      (libsource (lib "Resistors") (part "Resistor - 0.1%"))
    )
    (comp (ref "R207")
      (value "3k09")
      (footprint "RESC1608X55N")
      (description "Resistor - 0.1%")
      (fields
        (field (name "MANUFACTURER PART NUMBER") "R0603_3K09_0.1%_0.063W_10PPM")
        (field (name "MANUFACTURER") "GENERIC")
        (field (name "AUTHOR") "CERN DEM JLC")
      )
      (libsource (lib "Resistors") (part "Resistor - 0.1%"))
    )
    (comp (ref "R208")
      (value "33k2")
      (footprint "RESC1608X55N")
      (description "Resistor - 0.1%")
      (fields
        (field (name "MANUFACTURER PART NUMBER") "R0603_33K2_0.1%_0.063W_10PPM")
        (field (name "MANUFACTURER") "GENERIC")
        (field (name "AUTHOR") "CERN DEM JLC")
      )
      (libsource (lib "Resistors") (part "Resistor - 0.1%"))
    )
    (comp (ref "SH1")
      (value "Metal Screening Box 4x5 Pins")
      (footprint "MSBOX_WURTH_36103305")
      (description "Metal Screening Box 20 (4x5) Pins")
      (fields
        (field (name "MANUFACTURER PART NUMBER") "36103305")
        (field (name "MANUFACTURER") "WURTH")
        (field (name "AUTHOR") "CERN DEM JLC")
      )
      (libsource (lib "Eletro-mechanical") (part "Metal Screening Box - 4x5 pins"))
    )
    (comp (ref "SH2")
      (value "Metal Screening Box 4x5 Pins")
      (footprint "MSBOX_WURTH_36103305")
      (description "Metal Screening Box 20 (4x5) Pins")
      (fields
        (field (name "MANUFACTURER PART NUMBER") "36103305")
        (field (name "MANUFACTURER") "WURTH")
        (field (name "AUTHOR") "CERN DEM JLC")
      )
      (libsource (lib "Eletro-mechanical") (part "Metal Screening Box - 4x5 pins"))
    )
    (comp (ref "T13")
      (value "BSS138LT1G")
      (footprint "SOT95P240X110-3N")
      (description "N-CHANNEL MOSFET WITH DIODE")
      (fields (field (name "MANUFACTURER") "ON SEMICONDUCTOR") (field (name "AUTHOR") "CERN DEM JLC"))
      (libsource (lib "") (part "N-MOSFET-D 1G 2S 3D_1"))
    )
    (comp (ref "T14")
      (value "BSS138LT1G")
      (footprint "SOT95P240X110-3N")
      (description "N-CHANNEL MOSFET WITH DIODE")
      (fields (field (name "MANUFACTURER") "ON SEMICONDUCTOR") (field (name "AUTHOR") "CERN DEM JLC"))
      (libsource (lib "ICs And Semiconductors") (part "N-MOSFET-D 1G 2S 3D"))
    )
    (comp (ref "T15")
      (value "BSS138LT1G")
      (footprint "SOT95P240X110-3N")
      (description "N-CHANNEL MOSFET WITH DIODE")
      (fields (field (name "MANUFACTURER") "ON SEMICONDUCTOR") (field (name "AUTHOR") "CERN DEM JLC"))
      (libsource (lib "ICs And Semiconductors") (part "N-MOSFET-D 1G 2S 3D"))
    )
    (comp (ref "T16")
      (value "BSS138LT1G")
      (footprint "SOT95P240X110-3N")
      (description "N-CHANNEL MOSFET WITH DIODE")
      (fields (field (name "MANUFACTURER") "ON SEMICONDUCTOR") (field (name "AUTHOR") "CERN DEM JLC"))
      (libsource (lib "ICs And Semiconductors") (part "N-MOSFET-D 1G 2S 3D"))
    )
    (comp (ref "TP1")
      (value "Test Point")
      (footprint "TPS127")
      (fields (field (name "PART NUMBER") "SMD_PAD_1.27X1.27MM") (field (name "AUTHOR") "CERN DEM JLC"))
      (libsource (lib "Eletro-mechanical") (part "Test Point"))
    )
    (comp (ref "TP2")
      (value "Test Point")
      (footprint "TPS127")
      (fields (field (name "PART NUMBER") "SMD_PAD_1.27X1.27MM") (field (name "AUTHOR") "CERN DEM JLC"))
      (libsource (lib "Eletro-mechanical") (part "Test Point"))
    )
    (comp (ref "TP3")
      (value "Test Point")
      (footprint "TPS127")
      (fields (field (name "PART NUMBER") "SMD_PAD_1.27X1.27MM") (field (name "AUTHOR") "CERN DEM JLC"))
      (libsource (lib "Eletro-mechanical") (part "Test Point"))
    )
    (comp (ref "TP4")
      (value "Test Point")
      (footprint "TPS127")
      (fields (field (name "PART NUMBER") "SMD_PAD_1.27X1.27MM") (field (name "AUTHOR") "CERN DEM JLC"))
      (libsource (lib "Eletro-mechanical") (part "Test Point"))
    )
    (comp (ref "TP5")
      (value "Test Point")
      (footprint "TPS127")
      (fields (field (name "PART NUMBER") "SMD_PAD_1.27X1.27MM") (field (name "AUTHOR") "CERN DEM JLC"))
      (libsource (lib "Eletro-mechanical") (part "Test Point"))
    )
    (comp (ref "TP46")
      (value "Test Point")
      (footprint "TPS127")
      (fields (field (name "PART NUMBER") "SMD_PAD_1.27X1.27MM") (field (name "AUTHOR") "CERN DEM JLC"))
      (libsource (lib "Eletro-mechanical") (part "Test Point"))
    )
    (comp (ref "TR1")
      (value "1:2")
      (footprint "XFMR_MINI-CIRCUITS_DB1627")
      (description "50 OHMS 10 to 4000 MHz RF Transformer")
      (fields
        (field (name "MANUFACTURER PART NUMBER") "TCM2-43X+")
        (field (name "MANUFACTURER") "MINI-CIRCUITS")
        (field (name "AUTHOR") "CERN DEM BC")
      )
      (libsource (lib "Inductors & Transformers") (part "XFMR_MINI-CIRCUITS_TCM2-43X"))
    )
  )
  (nets
    (net (code "3") (name "/CDR_CLK_CLEAN3_N") (class "Default")
      (node (ref "IC46") (pin "2") (pinfunction "~{CLK0}_2") (pintype "input"))
    )
    (net (code "4") (name "/CDR_CLK_CLEAN3_P") (class "Default")
      (node (ref "IC46") (pin "1") (pinfunction "CLK0_1") (pintype "input"))
    )
    (net (code "5") (name "/EXT_100M_RF_IN") (class "Default")
      (node (ref "C411") (pin "1") (pinfunction "1_1") (pintype "passive"))
      (node (ref "J4") (pin "1") (pinfunction "1_1") (pintype "bidirectional"))
    )
    (net (code "6") (name "/EXT_100M_RF_IN_GND") (class "Default")
      (node (ref "C1") (pin "1") (pinfunction "1_1") (pintype "passive"))
      (node (ref "C202") (pin "2") (pinfunction "2_2") (pintype "passive"))
      (node (ref "J4") (pin "2") (pinfunction "2_2") (pintype "bidirectional"))
      (node (ref "R186") (pin "1") (pinfunction "1_1") (pintype "passive"))
      (node (ref "TR1") (pin "1") (pinfunction "P1_1") (pintype "passive"))
      (node (ref "TR1") (pin "2") (pinfunction "P1_2") (pintype "passive"))
    )
    (net (code "7") (name "/EXT_REF_IN_N") (class "Default")
      (node (ref "C201") (pin "2") (pinfunction "2_2") (pintype "passive"))
      (node (ref "IC46") (pin "6") (pinfunction "~{CLK1}_6") (pintype "input"))
      (node (ref "R106") (pin "1") (pinfunction "1_1") (pintype "passive"))
    )
    (net (code "8") (name "/EXT_REF_IN_P") (class "Default")
      (node (ref "C203") (pin "2") (pinfunction "2_2") (pintype "passive"))
      (node (ref "IC46") (pin "5") (pinfunction "CLK1_5") (pintype "input"))
      (node (ref "R106") (pin "2") (pinfunction "2_2") (pintype "passive"))
    )
    (net (code "9") (name "/HMC_SPI_SCLK") (class "Default")
      (node (ref "IC40") (pin "32") (pinfunction "SCK_32") (pintype "input"))
      (node (ref "R108") (pin "2") (pinfunction "2_2") (pintype "passive"))
      (node (ref "TP2") (pin "1") (pinfunction "1_1") (pintype "bidirectional"))
    )
    (net (code "10") (name "/HMC_SPI_SDATA") (class "Default")
      (node (ref "IC40") (pin "31") (pinfunction "SDI_31") (pintype "input"))
      (node (ref "TP3") (pin "1") (pinfunction "1_1") (pintype "bidirectional"))
    )
    (net (code "11") (name "/HMC_SPI_SDO") (class "Default")
      (node (ref "IC40") (pin "33") (pinfunction "LD_SDO_33") (pintype "output"))
      (node (ref "TP4") (pin "1") (pinfunction "1_1") (pintype "bidirectional"))
    )
    (net (code "12") (name "/HMC_SPI_SEN") (class "Default")
      (node (ref "IC40") (pin "30") (pinfunction "SEN_30") (pintype "input"))
      (node (ref "R107") (pin "2") (pinfunction "2_2") (pintype "passive"))
      (node (ref "TP5") (pin "1") (pinfunction "1_1") (pintype "bidirectional"))
    )
    (net (code "13") (name "/P3V3_CLKDIS1F") (class "Default")
      (node (ref "C210") (pin "2") (pinfunction "2_2") (pintype "passive"))
      (node (ref "C220") (pin "2") (pinfunction "2_2") (pintype "passive"))
      (node (ref "C222") (pin "2") (pinfunction "2_2") (pintype "passive"))
      (node (ref "C223") (pin "2") (pinfunction "2_2") (pintype "passive"))
      (node (ref "C408") (pin "1") (pinfunction "1_1") (pintype "passive"))
      (node (ref "C409") (pin "2") (pinfunction "2_2") (pintype "passive"))
      (node (ref "C410") (pin "2") (pinfunction "2_2") (pintype "passive"))
      (node (ref "IC46") (pin "10") (pinfunction "VCC_10") (pintype "power_in"))
      (node (ref "IC46") (pin "15") (pinfunction "VCC_15") (pintype "power_in"))
      (node (ref "IC46") (pin "16") (pinfunction "VCC_16") (pintype "power_in"))
      (node (ref "IC46") (pin "25") (pinfunction "VCC_25") (pintype "power_in"))
      (node (ref "IC46") (pin "26") (pinfunction "VCC_26") (pintype "power_in"))
      (node (ref "IC46") (pin "31") (pinfunction "VCC_31") (pintype "power_in"))
      (node (ref "L24") (pin "2") (pinfunction "2_2") (pintype "passive"))
    )
    (net (code "14") (name "/P5V0_CLK_L") (class "Default")
      (node (ref "C15") (pin "2") (pinfunction "2_2") (pintype "passive"))
      (node (ref "C16") (pin "2") (pinfunction "2_2") (pintype "passive"))
      (node (ref "IC40") (pin "24") (pinfunction "NC_24") (pintype "passive"))
      (node (ref "IC40") (pin "25") (pinfunction "VCC2_25") (pintype "power_in"))
      (node (ref "IC40") (pin "26") (pinfunction "NC_26") (pintype "passive"))
      (node (ref "IC40") (pin "27") (pinfunction "VCC1_27") (pintype "power_in"))
      (node (ref "L37") (pin "1") (pinfunction "1_1") (pintype "passive"))
    )
    (net (code "15") (name "/P6V0_LDO") (class "Default")
      (node (ref "C337") (pin "2") (pinfunction "2_2") (pintype "passive"))
      (node (ref "C88") (pin "2") (pinfunction "2_2") (pintype "passive"))
      (node (ref "L13") (pin "2") (pinfunction "2_2") (pintype "passive"))
      (node (ref "L22") (pin "1") (pinfunction "1_1") (pintype "passive"))
      (node (ref "L23") (pin "1") (pinfunction "1_1") (pintype "passive"))
    )
    (net (code "16") (name "/P6V0_LDO_IN2") (class "Default")
      (node (ref "C339") (pin "2") (pinfunction "2_2") (pintype "passive"))
      (node (ref "IC22") (pin "1") (pinfunction "IN_1") (pintype "input"))
      (node (ref "IC22") (pin "2") (pinfunction "IN_2") (pintype "input"))
      (node (ref "IC22") (pin "6") (pinfunction "PGFB_6") (pintype "input"))
      (node (ref "L23") (pin "2") (pinfunction "2_2") (pintype "passive"))
    )
    (net (code "17") (name "/P6V0_LDO_IN3") (class "Default")
      (node (ref "C340") (pin "2") (pinfunction "2_2") (pintype "passive"))
      (node (ref "IC23") (pin "1") (pinfunction "IN_1") (pintype "input"))
      (node (ref "IC23") (pin "2") (pinfunction "IN_2") (pintype "input"))
      (node (ref "IC23") (pin "6") (pinfunction "PGFB_6") (pintype "input"))
      (node (ref "L22") (pin "2") (pinfunction "2_2") (pintype "passive"))
    )
    (net (code "18") (name "/REF0_LO_N") (class "Default")
      (node (ref "C224") (pin "2") (pinfunction "2_2") (pintype "passive"))
    )
    (net (code "19") (name "/REF0_LO_P") (class "Default")
      (node (ref "C227") (pin "2") (pinfunction "2_2") (pintype "passive"))
    )
    (net (code "20") (name "/REF1_LO_N") (class "Default")
      (node (ref "C225") (pin "2") (pinfunction "2_2") (pintype "passive"))
    )
    (net (code "21") (name "/REF1_LO_P") (class "Default")
      (node (ref "C226") (pin "2") (pinfunction "2_2") (pintype "passive"))
    )
    (net (code "22") (name "/REF_CLK_SRC_EXT_SEL") (class "Default")
      (node (ref "IC46") (pin "32") (pinfunction "IN_SEL_32") (pintype "input"))
      (node (ref "TP1") (pin "1") (pinfunction "1_1") (pintype "bidirectional"))
    )
    (net (code "23") (name "/REF_HMC_P") (class "Default")
      (node (ref "C204") (pin "1") (pinfunction "1_1") (pintype "passive"))
      (node (ref "IC46") (pin "14") (pinfunction "Q6_14") (pintype "output"))
      (node (ref "R102") (pin "1") (pinfunction "1_1") (pintype "passive"))
    )
    (net (code "24") (name "/VCCCP") (class "Default")
      (node (ref "C341") (pin "2") (pinfunction "2_2") (pintype "passive"))
      (node (ref "C85") (pin "2") (pinfunction "2_2") (pintype "passive"))
      (node (ref "C86") (pin "2") (pinfunction "2_2") (pintype "passive"))
      (node (ref "IC40") (pin "3") (pinfunction "VPPCP_3") (pintype "power_in"))
      (node (ref "IC40") (pin "7") (pinfunction "VDDLS_7") (pintype "power_in"))
      (node (ref "L21") (pin "1") (pinfunction "1_1") (pintype "passive"))
    )
    (net (code "25") (name "/VTUNE") (class "Default")
      (node (ref "C4") (pin "2") (pinfunction "2_2") (pintype "passive"))
      (node (ref "C511") (pin "2") (pinfunction "2_2") (pintype "passive"))
      (node (ref "IC40") (pin "21") (pinfunction "NC_21") (pintype "passive"))
      (node (ref "IC40") (pin "22") (pinfunction "NC_22") (pintype "passive"))
      (node (ref "IC40") (pin "23") (pinfunction "VTUNE_23") (pintype "input"))
      (node (ref "R207") (pin "1") (pinfunction "1_1") (pintype "passive"))
      (node (ref "TP46") (pin "1") (pinfunction "1_1") (pintype "bidirectional"))
    )
    (net (code "28") (name "GND") (class "Default")
      (node (ref "C1") (pin "2") (pinfunction "2_2") (pintype "passive"))
      (node (ref "C10") (pin "1") (pinfunction "1_1") (pintype "passive"))
      (node (ref "C110") (pin "1") (pinfunction "1_1") (pintype "passive"))
      (node (ref "C15") (pin "1") (pinfunction "1_1") (pintype "passive"))
      (node (ref "C16") (pin "1") (pinfunction "1_1") (pintype "passive"))
      (node (ref "C2") (pin "1") (pinfunction "1_1") (pintype "passive"))
      (node (ref "C200") (pin "1") (pinfunction "1_1") (pintype "passive"))
      (node (ref "C202") (pin "1") (pinfunction "1_1") (pintype "passive"))
      (node (ref "C210") (pin "1") (pinfunction "1_1") (pintype "passive"))
      (node (ref "C220") (pin "1") (pinfunction "1_1") (pintype "passive"))
      (node (ref "C221") (pin "1") (pinfunction "1_1") (pintype "passive"))
      (node (ref "C222") (pin "1") (pinfunction "1_1") (pintype "passive"))
      (node (ref "C223") (pin "1") (pinfunction "1_1") (pintype "passive"))
      (node (ref "C3") (pin "1") (pinfunction "1_1") (pintype "passive"))
      (node (ref "C335") (pin "1") (pinfunction "1_1") (pintype "passive"))
      (node (ref "C337") (pin "1") (pinfunction "1_1") (pintype "passive"))
      (node (ref "C338") (pin "1") (pinfunction "1_1") (pintype "passive"))
      (node (ref "C339") (pin "1") (pinfunction "1_1") (pintype "passive"))
      (node (ref "C340") (pin "1") (pinfunction "1_1") (pintype "passive"))
      (node (ref "C341") (pin "1") (pinfunction "1_1") (pintype "passive"))
      (node (ref "C4") (pin "1") (pinfunction "1_1") (pintype "passive"))
      (node (ref "C408") (pin "2") (pinfunction "2_2") (pintype "passive"))
      (node (ref "C409") (pin "1") (pinfunction "1_1") (pintype "passive"))
      (node (ref "C410") (pin "1") (pinfunction "1_1") (pintype "passive"))
      (node (ref "C471") (pin "2") (pinfunction "2_2") (pintype "passive"))
      (node (ref "C472") (pin "2") (pinfunction "2_2") (pintype "passive"))
      (node (ref "C5") (pin "1") (pinfunction "1_1") (pintype "passive"))
      (node (ref "C511") (pin "1") (pinfunction "1_1") (pintype "passive"))
      (node (ref "C512") (pin "1") (pinfunction "1_1") (pintype "passive"))
      (node (ref "C513") (pin "1") (pinfunction "1_1") (pintype "passive"))
      (node (ref "C552") (pin "1") (pinfunction "1_1") (pintype "passive"))
      (node (ref "C554") (pin "1") (pinfunction "1_1") (pintype "passive"))
      (node (ref "C85") (pin "1") (pinfunction "1_1") (pintype "passive"))
      (node (ref "C86") (pin "1") (pinfunction "1_1") (pintype "passive"))
      (node (ref "C88") (pin "1") (pinfunction "1_1") (pintype "passive"))
      (node (ref "C89") (pin "1") (pinfunction "1_1") (pintype "passive"))
      (node (ref "C9") (pin "1") (pinfunction "1_1") (pintype "passive"))
      (node (ref "C90") (pin "1") (pinfunction "1_1") (pintype "passive"))
      (node (ref "C91") (pin "1") (pinfunction "1_1") (pintype "passive"))
      (node (ref "C92") (pin "1") (pinfunction "1_1") (pintype "passive"))
      (node (ref "C93") (pin "1") (pinfunction "1_1") (pintype "passive"))
      (node (ref "C94") (pin "1") (pinfunction "1_1") (pintype "passive"))
      (node (ref "C95") (pin "1") (pinfunction "1_1") (pintype "passive"))
      (node (ref "IC22") (pin "11") (pinfunction "GND_11") (pintype "power_in"))
      (node (ref "IC22") (pin "3") (pinfunction "EN/UV_3") (pintype "input"))
      (node (ref "IC22") (pin "5") (pinfunction "ILIM_5") (pintype "input"))
      (node (ref "IC22") (pin "8") (pinfunction "GND_8") (pintype "power_in"))
      (node (ref "IC23") (pin "11") (pinfunction "GND_11") (pintype "power_in"))
      (node (ref "IC23") (pin "3") (pinfunction "EN/UV_3") (pintype "input"))
      (node (ref "IC23") (pin "5") (pinfunction "ILIM_5") (pintype "input"))
      (node (ref "IC23") (pin "8") (pinfunction "GND_8") (pintype "power_in"))
      (node (ref "IC40") (pin "41") (pinfunction "EP_41") (pintype "power_in"))
      (node (ref "IC40") (pin "5") (pinfunction "NC_5") (pintype "passive"))
      (node (ref "IC40") (pin "6") (pinfunction "NC_6") (pintype "passive"))
      (node (ref "IC46") (pin "33") (pinfunction "VEE_33") (pintype "power_in"))
      (node (ref "J10") (pin "2") (pinfunction "2_2") (pintype "bidirectional"))
      (node (ref "J12") (pin "2") (pinfunction "2_2") (pintype "bidirectional"))
      (node (ref "J16") (pin "2") (pinfunction "2_2") (pintype "bidirectional"))
      (node (ref "J9") (pin "2") (pinfunction "2_2") (pintype "bidirectional"))
      (node (ref "R107") (pin "1") (pinfunction "1_1") (pintype "passive"))
      (node (ref "R108") (pin "1") (pinfunction "1_1") (pintype "passive"))
      (node (ref "R109") (pin "2") (pinfunction "2_2") (pintype "passive"))
      (node (ref "R110") (pin "2") (pinfunction "2_2") (pintype "passive"))
      (node (ref "R111") (pin "2") (pinfunction "2_2") (pintype "passive"))
      (node (ref "R112") (pin "2") (pinfunction "2_2") (pintype "passive"))
      (node (ref "R128") (pin "2") (pinfunction "2_2") (pintype "passive"))
      (node (ref "R186") (pin "2") (pinfunction "2_2") (pintype "passive"))
      (node (ref "R204") (pin "1") (pinfunction "1_1") (pintype "passive"))
      (node (ref "R208") (pin "1") (pinfunction "1_1") (pintype "passive"))
      (node (ref "R59") (pin "2") (pinfunction "2_2") (pintype "passive"))
      (node (ref "R95") (pin "1") (pinfunction "1_1") (pintype "passive"))
      (node (ref "R95") (pin "2") (pinfunction "2_2") (pintype "passive"))
      (node (ref "SH1") (pin "1") (pinfunction "1_1") (pintype "passive"))
      (node (ref "SH1") (pin "10") (pinfunction "10_10") (pintype "passive"))
      (node (ref "SH1") (pin "11") (pinfunction "11_11") (pintype "passive"))
      (node (ref "SH1") (pin "12") (pinfunction "12_12") (pintype "passive"))
      (node (ref "SH1") (pin "13") (pinfunction "13_13") (pintype "passive"))
      (node (ref "SH1") (pin "14") (pinfunction "14_14") (pintype "passive"))
      (node (ref "SH1") (pin "15") (pinfunction "15_15") (pintype "passive"))
      (node (ref "SH1") (pin "16") (pinfunction "16_16") (pintype "passive"))
      (node (ref "SH1") (pin "17") (pinfunction "17_17") (pintype "passive"))
      (node (ref "SH1") (pin "18") (pinfunction "18_18") (pintype "passive"))
      (node (ref "SH1") (pin "19") (pinfunction "19_19") (pintype "passive"))
      (node (ref "SH1") (pin "2") (pinfunction "2_2") (pintype "passive"))
      (node (ref "SH1") (pin "20") (pinfunction "20_20") (pintype "passive"))
      (node (ref "SH1") (pin "3") (pinfunction "3_3") (pintype "passive"))
      (node (ref "SH1") (pin "4") (pinfunction "4_4") (pintype "passive"))
      (node (ref "SH1") (pin "5") (pinfunction "5_5") (pintype "passive"))
      (node (ref "SH1") (pin "6") (pinfunction "6_6") (pintype "passive"))
      (node (ref "SH1") (pin "7") (pinfunction "7_7") (pintype "passive"))
      (node (ref "SH1") (pin "8") (pinfunction "8_8") (pintype "passive"))
      (node (ref "SH1") (pin "9") (pinfunction "9_9") (pintype "passive"))
      (node (ref "SH2") (pin "1") (pinfunction "1_1") (pintype "passive"))
      (node (ref "SH2") (pin "10") (pinfunction "10_10") (pintype "passive"))
      (node (ref "SH2") (pin "11") (pinfunction "11_11") (pintype "passive"))
      (node (ref "SH2") (pin "12") (pinfunction "12_12") (pintype "passive"))
      (node (ref "SH2") (pin "13") (pinfunction "13_13") (pintype "passive"))
      (node (ref "SH2") (pin "14") (pinfunction "14_14") (pintype "passive"))
      (node (ref "SH2") (pin "15") (pinfunction "15_15") (pintype "passive"))
      (node (ref "SH2") (pin "16") (pinfunction "16_16") (pintype "passive"))
      (node (ref "SH2") (pin "17") (pinfunction "17_17") (pintype "passive"))
      (node (ref "SH2") (pin "18") (pinfunction "18_18") (pintype "passive"))
      (node (ref "SH2") (pin "19") (pinfunction "19_19") (pintype "passive"))
      (node (ref "SH2") (pin "2") (pinfunction "2_2") (pintype "passive"))
      (node (ref "SH2") (pin "20") (pinfunction "20_20") (pintype "passive"))
      (node (ref "SH2") (pin "3") (pinfunction "3_3") (pintype "passive"))
      (node (ref "SH2") (pin "4") (pinfunction "4_4") (pintype "passive"))
      (node (ref "SH2") (pin "5") (pinfunction "5_5") (pintype "passive"))
      (node (ref "SH2") (pin "6") (pinfunction "6_6") (pintype "passive"))
      (node (ref "SH2") (pin "7") (pinfunction "7_7") (pintype "passive"))
      (node (ref "SH2") (pin "8") (pinfunction "8_8") (pintype "passive"))
      (node (ref "SH2") (pin "9") (pinfunction "9_9") (pintype "passive"))
      (node (ref "T13") (pin "1") (pinfunction "G_1") (pintype "passive"))
      (node (ref "T13") (pin "2") (pinfunction "S_2") (pintype "passive"))
      (node (ref "T14") (pin "2") (pinfunction "S_2") (pintype "passive"))
      (node (ref "T15") (pin "2") (pinfunction "S_2") (pintype "passive"))
      (node (ref "T16") (pin "1") (pinfunction "G_1") (pintype "passive"))
      (node (ref "T16") (pin "2") (pinfunction "S_2") (pintype "passive"))
      (node (ref "TR1") (pin "5") (pinfunction "NC_5") (pintype "passive"))
    )
    (net (code "29") (name "Net-(C10-Pad2)") (class "Default")
      (node (ref "C10") (pin "2") (pinfunction "2_2") (pintype "passive"))
      (node (ref "C201") (pin "1") (pinfunction "1_1") (pintype "passive"))
      (node (ref "TR1") (pin "4") (pinfunction "S1_4") (pintype "passive"))
    )
    (net (code "30") (name "Net-(C11-Pad1)") (class "Default")
      (node (ref "C11") (pin "1") (pinfunction "1_1") (pintype "passive"))
      (node (ref "C13") (pin "1") (pinfunction "1_1") (pintype "passive"))
    )
    (net (code "31") (name "Net-(C11-Pad2)") (class "Default")
      (node (ref "C11") (pin "2") (pinfunction "2_2") (pintype "passive"))
      (node (ref "J9") (pin "1") (pinfunction "1_1") (pintype "bidirectional"))
    )
    (net (code "32") (name "Net-(C12-Pad1)") (class "Default")
      (node (ref "C12") (pin "1") (pinfunction "1_1") (pintype "passive"))
      (node (ref "C14") (pin "1") (pinfunction "1_1") (pintype "passive"))
    )
    (net (code "33") (name "Net-(C12-Pad2)") (class "Default")
      (node (ref "C12") (pin "2") (pinfunction "2_2") (pintype "passive"))
      (node (ref "J10") (pin "1") (pinfunction "1_1") (pintype "bidirectional"))
    )
    (net (code "34") (name "Net-(C111-Pad2)") (class "Default")
      (node (ref "C111") (pin "2") (pinfunction "2_2") (pintype "passive"))
      (node (ref "J16") (pin "1") (pinfunction "1_1") (pintype "bidirectional"))
    )
    (net (code "35") (name "Net-(C113-Pad2)") (class "Default")
      (node (ref "C113") (pin "2") (pinfunction "2_2") (pintype "passive"))
      (node (ref "J12") (pin "1") (pinfunction "1_1") (pintype "bidirectional"))
    )
    (net (code "36") (name "Net-(C200-Pad2)") (class "Default")
      (node (ref "C200") (pin "2") (pinfunction "2_2") (pintype "passive"))
      (node (ref "R97") (pin "1") (pinfunction "1_1") (pintype "passive"))
    )
    (net (code "37") (name "Net-(C203-Pad1)") (class "Default")
      (node (ref "C203") (pin "1") (pinfunction "1_1") (pintype "passive"))
      (node (ref "C9") (pin "2") (pinfunction "2_2") (pintype "passive"))
      (node (ref "TR1") (pin "6") (pinfunction "S1_6") (pintype "passive"))
    )
    (net (code "38") (name "Net-(C411-Pad2)") (class "Default")
      (node (ref "C411") (pin "2") (pinfunction "2_2") (pintype "passive"))
      (node (ref "TR1") (pin "3") (pinfunction "P1_3") (pintype "passive"))
    )
    (net (code "39") (name "Net-(C512-Pad2)") (class "Default")
      (node (ref "C512") (pin "2") (pinfunction "2_2") (pintype "passive"))
      (node (ref "C552") (pin "2") (pinfunction "2_2") (pintype "passive"))
      (node (ref "R206") (pin "1") (pinfunction "1_1") (pintype "passive"))
    )
    (net (code "40") (name "Net-(IC22-SET)") (class "Default")
      (node (ref "C472") (pin "1") (pinfunction "1_1") (pintype "passive"))
      (node (ref "IC22") (pin "7") (pinfunction "SET_7") (pintype "input"))
      (node (ref "R204") (pin "2") (pinfunction "2_2") (pintype "passive"))
    )
    (net (code "41") (name "Net-(IC23-SET)") (class "Default")
      (node (ref "C471") (pin "1") (pinfunction "1_1") (pintype "passive"))
      (node (ref "IC23") (pin "7") (pinfunction "SET_7") (pintype "input"))
      (node (ref "R208") (pin "2") (pinfunction "2_2") (pintype "passive"))
    )
    (net (code "42") (name "Net-(IC40-BIAS)") (class "Default")
      (node (ref "C87") (pin "1") (pinfunction "1_1") (pintype "passive"))
      (node (ref "IC40") (pin "40") (pinfunction "BIAS_40") (pintype "passive"))
    )
    (net (code "43") (name "Net-(IC40-CP)") (class "Default")
      (node (ref "C3") (pin "2") (pinfunction "2_2") (pintype "passive"))
      (node (ref "C513") (pin "2") (pinfunction "2_2") (pintype "passive"))
      (node (ref "IC40") (pin "4") (pinfunction "CP_4") (pintype "output"))
      (node (ref "R206") (pin "2") (pinfunction "2_2") (pintype "passive"))
      (node (ref "R207") (pin "2") (pinfunction "2_2") (pintype "passive"))
    )
    (net (code "44") (name "Net-(IC40-DVDD3V)") (class "Default")
      (node (ref "C338") (pin "2") (pinfunction "2_2") (pintype "passive"))
      (node (ref "C91") (pin "2") (pinfunction "2_2") (pintype "passive"))
      (node (ref "IC40") (pin "16") (pinfunction "DVDD3V_16") (pintype "power_in"))
      (node (ref "R103") (pin "1") (pinfunction "1_1") (pintype "passive"))
    )
    (net (code "45") (name "Net-(IC40-RF_N)") (class "Default")
      (node (ref "C14") (pin "2") (pinfunction "2_2") (pintype "passive"))
      (node (ref "IC40") (pin "28") (pinfunction "RF_N_28") (pintype "output"))
    )
    (net (code "46") (name "Net-(IC40-RF_P)") (class "Default")
      (node (ref "C13") (pin "2") (pinfunction "2_2") (pintype "passive"))
      (node (ref "IC40") (pin "29") (pinfunction "RF_P_29") (pintype "output"))
    )
    (net (code "47") (name "Net-(IC40-XREFP)") (class "Default")
      (node (ref "C204") (pin "2") (pinfunction "2_2") (pintype "passive"))
      (node (ref "IC40") (pin "15") (pinfunction "XREFP_15") (pintype "input"))
      (node (ref "R97") (pin "2") (pinfunction "2_2") (pintype "passive"))
    )
    (net (code "48") (name "Net-(IC46-Q0)") (class "Default")
      (node (ref "C227") (pin "1") (pinfunction "1_1") (pintype "passive"))
      (node (ref "IC46") (pin "30") (pinfunction "Q0_30") (pintype "output"))
      (node (ref "R109") (pin "1") (pinfunction "1_1") (pintype "passive"))
    )
    (net (code "49") (name "Net-(IC46-Q1)") (class "Default")
      (node (ref "C226") (pin "1") (pinfunction "1_1") (pintype "passive"))
      (node (ref "IC46") (pin "28") (pinfunction "Q1_28") (pintype "output"))
      (node (ref "R111") (pin "1") (pinfunction "1_1") (pintype "passive"))
    )
    (net (code "50") (name "Net-(IC46-Q3)") (class "Default")
      (node (ref "C113") (pin "1") (pinfunction "1_1") (pintype "passive"))
      (node (ref "IC46") (pin "22") (pinfunction "Q3_22") (pintype "output"))
      (node (ref "R59") (pin "1") (pinfunction "1_1") (pintype "passive"))
    )
    (net (code "51") (name "Net-(IC46-VREF0)") (class "Default")
      (node (ref "IC46") (pin "3") (pinfunction "VREF0_3") (pintype "input"))
      (node (ref "R104") (pin "1") (pinfunction "1_1") (pintype "passive"))
    )
    (net (code "52") (name "Net-(IC46-VREF1)") (class "Default")
      (node (ref "IC46") (pin "8") (pinfunction "VREF1_8") (pintype "input"))
      (node (ref "R105") (pin "1") (pinfunction "1_1") (pintype "passive"))
    )
    (net (code "53") (name "Net-(IC46-VT0)") (class "Default")
      (node (ref "C221") (pin "2") (pinfunction "2_2") (pintype "passive"))
      (node (ref "IC46") (pin "4") (pinfunction "VT0_4") (pintype "passive"))
      (node (ref "R104") (pin "2") (pinfunction "2_2") (pintype "passive"))
    )
    (net (code "54") (name "Net-(IC46-VT1)") (class "Default")
      (node (ref "C554") (pin "2") (pinfunction "2_2") (pintype "passive"))
      (node (ref "IC46") (pin "7") (pinfunction "VT1_7") (pintype "passive"))
      (node (ref "R105") (pin "2") (pinfunction "2_2") (pintype "passive"))
    )
    (net (code "55") (name "Net-(IC46-~{Q0})") (class "Default")
      (node (ref "C224") (pin "1") (pinfunction "1_1") (pintype "passive"))
      (node (ref "IC46") (pin "29") (pinfunction "~{Q0}_29") (pintype "output"))
      (node (ref "R110") (pin "1") (pinfunction "1_1") (pintype "passive"))
    )
    (net (code "56") (name "Net-(IC46-~{Q1})") (class "Default")
      (node (ref "C225") (pin "1") (pinfunction "1_1") (pintype "passive"))
      (node (ref "IC46") (pin "27") (pinfunction "~{Q1}_27") (pintype "output"))
      (node (ref "R112") (pin "1") (pinfunction "1_1") (pintype "passive"))
    )
    (net (code "57") (name "Net-(IC46-~{Q3})") (class "Default")
      (node (ref "C111") (pin "1") (pinfunction "1_1") (pintype "passive"))
      (node (ref "IC46") (pin "21") (pinfunction "~{Q3}_21") (pintype "output"))
      (node (ref "R128") (pin "1") (pinfunction "1_1") (pintype "passive"))
    )
    (net (code "58") (name "Net-(IC46-~{Q6})") (class "Default")
      (node (ref "IC46") (pin "13") (pinfunction "~{Q6}_13") (pintype "output"))
      (node (ref "R101") (pin "1") (pinfunction "1_1") (pintype "passive"))
    )
    (net (code "59") (name "Net-(T13-D)") (class "Default")
      (node (ref "C110") (pin "2") (pinfunction "2_2") (pintype "passive"))
      (node (ref "R101") (pin "2") (pinfunction "2_2") (pintype "passive"))
      (node (ref "R102") (pin "2") (pinfunction "2_2") (pintype "passive"))
      (node (ref "T13") (pin "3") (pinfunction "D_3") (pintype "passive"))
    )
    (net (code "60") (name "Net-(T14-D)") (class "Default")
      (node (ref "R75") (pin "1") (pinfunction "1_1") (pintype "passive"))
      (node (ref "T14") (pin "3") (pinfunction "D_3") (pintype "passive"))
    )
    (net (code "61") (name "Net-(T14-G)") (class "Default")
      (node (ref "R127") (pin "1") (pinfunction "1_1") (pintype "passive"))
      (node (ref "T14") (pin "1") (pinfunction "G_1") (pintype "passive"))
      (node (ref "T15") (pin "1") (pinfunction "G_1") (pintype "passive"))
      (node (ref "T16") (pin "3") (pinfunction "D_3") (pintype "passive"))
    )
    (net (code "62") (name "Net-(T15-D)") (class "Default")
      (node (ref "R76") (pin "1") (pinfunction "1_1") (pintype "passive"))
      (node (ref "T15") (pin "3") (pinfunction "D_3") (pintype "passive"))
    )
    (net (code "63") (name "P3V3_CLK") (class "Default")
      (node (ref "C335") (pin "2") (pinfunction "2_2") (pintype "passive"))
      (node (ref "C5") (pin "2") (pinfunction "2_2") (pintype "passive"))
      (node (ref "C87") (pin "2") (pinfunction "2_2") (pintype "passive"))
      (node (ref "C89") (pin "2") (pinfunction "2_2") (pintype "passive"))
      (node (ref "C90") (pin "2") (pinfunction "2_2") (pintype "passive"))
      (node (ref "C92") (pin "2") (pinfunction "2_2") (pintype "passive"))
      (node (ref "C93") (pin "2") (pinfunction "2_2") (pintype "passive"))
      (node (ref "C94") (pin "2") (pinfunction "2_2") (pintype "passive"))
      (node (ref "C95") (pin "2") (pinfunction "2_2") (pintype "passive"))
      (node (ref "IC23") (pin "10") (pinfunction "OUT_10") (pintype "output"))
      (node (ref "IC23") (pin "9") (pinfunction "OUTS_9") (pintype "output"))
      (node (ref "IC40") (pin "1") (pinfunction "AVDD_1") (pintype "power_in"))
      (node (ref "IC40") (pin "10") (pinfunction "RVDD_10") (pintype "power_in"))
      (node (ref "IC40") (pin "17") (pinfunction "CEN_17") (pintype "input"))
      (node (ref "IC40") (pin "18") (pinfunction "NC_18") (pintype "passive"))
      (node (ref "IC40") (pin "19") (pinfunction "NC_19") (pintype "passive"))
      (node (ref "IC40") (pin "20") (pinfunction "NC_20") (pintype "passive"))
      (node (ref "IC40") (pin "35") (pinfunction "VCCHF_35") (pintype "power_in"))
      (node (ref "IC40") (pin "36") (pinfunction "VCCPS_36") (pintype "power_in"))
      (node (ref "IC40") (pin "39") (pinfunction "VCCPD_39") (pintype "power_in"))
      (node (ref "R103") (pin "2") (pinfunction "2_2") (pintype "passive"))
      (node (ref "R76") (pin "2") (pinfunction "2_2") (pintype "passive"))
    )
    (net (code "64") (name "P3V3_CLKDIS1") (class "Default")
      (node (ref "L24") (pin "1") (pinfunction "1_1") (pintype "passive"))
    )
    (net (code "65") (name "P5V0_CLK") (class "Default")
      (node (ref "C2") (pin "2") (pinfunction "2_2") (pintype "passive"))
      (node (ref "IC22") (pin "10") (pinfunction "OUT_10") (pintype "output"))
      (node (ref "IC22") (pin "9") (pinfunction "OUTS_9") (pintype "output"))
      (node (ref "L21") (pin "2") (pinfunction "2_2") (pintype "passive"))
      (node (ref "L37") (pin "2") (pinfunction "2_2") (pintype "passive"))
      (node (ref "R75") (pin "2") (pinfunction "2_2") (pintype "passive"))
    )
    (net (code "66") (name "P6V0A") (class "Default")
      (node (ref "L13") (pin "1") (pinfunction "1_1") (pintype "passive"))
      (node (ref "R127") (pin "2") (pinfunction "2_2") (pintype "passive"))
    )
    (net (code "67") (name "unconnected-(IC22-PG-Pad4)") (class "Default")
      (node (ref "IC22") (pin "4") (pinfunction "PG_4") (pintype "output+no_connect"))
    )
    (net (code "68") (name "unconnected-(IC23-PG-Pad4)") (class "Default")
      (node (ref "IC23") (pin "4") (pinfunction "PG_4") (pintype "output+no_connect"))
    )
    (net (code "69") (name "unconnected-(IC40-NC-Pad2)") (class "Default")
      (node (ref "IC40") (pin "2") (pinfunction "NC_2") (pintype "passive+no_connect"))
    )
    (net (code "70") (name "unconnected-(IC40-NC-Pad8)") (class "Default")
      (node (ref "IC40") (pin "8") (pinfunction "NC_8") (pintype "passive+no_connect"))
    )
    (net (code "71") (name "unconnected-(IC40-NC-Pad9)") (class "Default")
      (node (ref "IC40") (pin "9") (pinfunction "NC_9") (pintype "passive+no_connect"))
    )
    (net (code "72") (name "unconnected-(IC40-NC-Pad11)") (class "Default")
      (node (ref "IC40") (pin "11") (pinfunction "NC_11") (pintype "passive+no_connect"))
    )
    (net (code "73") (name "unconnected-(IC40-NC-Pad12)") (class "Default")
      (node (ref "IC40") (pin "12") (pinfunction "NC_12") (pintype "passive+no_connect"))
    )
    (net (code "74") (name "unconnected-(IC40-NC-Pad13)") (class "Default")
      (node (ref "IC40") (pin "13") (pinfunction "NC_13") (pintype "passive+no_connect"))
    )
    (net (code "75") (name "unconnected-(IC40-NC-Pad14)") (class "Default")
      (node (ref "IC40") (pin "14") (pinfunction "NC_14") (pintype "passive+no_connect"))
    )
    (net (code "76") (name "unconnected-(IC40-NC-Pad34)") (class "Default")
      (node (ref "IC40") (pin "34") (pinfunction "NC_34") (pintype "passive+no_connect"))
    )
    (net (code "77") (name "unconnected-(IC40-NC-Pad37)") (class "Default")
      (node (ref "IC40") (pin "37") (pinfunction "NC_37") (pintype "passive+no_connect"))
    )
    (net (code "78") (name "unconnected-(IC40-NC-Pad38)") (class "Default")
      (node (ref "IC40") (pin "38") (pinfunction "NC_38") (pintype "passive+no_connect"))
    )
    (net (code "79") (name "unconnected-(IC46-NC-Pad9)") (class "Default")
      (node (ref "IC46") (pin "9") (pinfunction "NC_9") (pintype "passive+no_connect"))
    )
    (net (code "80") (name "unconnected-(IC46-Q2-Pad24)") (class "Default")
      (node (ref "IC46") (pin "24") (pinfunction "Q2_24") (pintype "output"))
    )
    (net (code "81") (name "unconnected-(IC46-Q4-Pad20)") (class "Default")
      (node (ref "IC46") (pin "20") (pinfunction "Q4_20") (pintype "output"))
    )
    (net (code "82") (name "unconnected-(IC46-Q5-Pad18)") (class "Default")
      (node (ref "IC46") (pin "18") (pinfunction "Q5_18") (pintype "output"))
    )
    (net (code "83") (name "unconnected-(IC46-Q7-Pad12)") (class "Default")
      (node (ref "IC46") (pin "12") (pinfunction "Q7_12") (pintype "output"))
    )
    (net (code "84") (name "unconnected-(IC46-~{Q2}-Pad23)") (class "Default")
      (node (ref "IC46") (pin "23") (pinfunction "~{Q2}_23") (pintype "output"))
    )
    (net (code "85") (name "unconnected-(IC46-~{Q4}-Pad19)") (class "Default")
      (node (ref "IC46") (pin "19") (pinfunction "~{Q4}_19") (pintype "output"))
    )
    (net (code "86") (name "unconnected-(IC46-~{Q5}-Pad17)") (class "Default")
      (node (ref "IC46") (pin "17") (pinfunction "~{Q5}_17") (pintype "output"))
    )
    (net (code "87") (name "unconnected-(IC46-~{Q7}-Pad11)") (class "Default")
      (node (ref "IC46") (pin "11") (pinfunction "~{Q7}_11") (pintype "output"))
    )
  )
)
